# MainBoardV2.net
KiCad netlist of a schematic drawn in Altium Designer
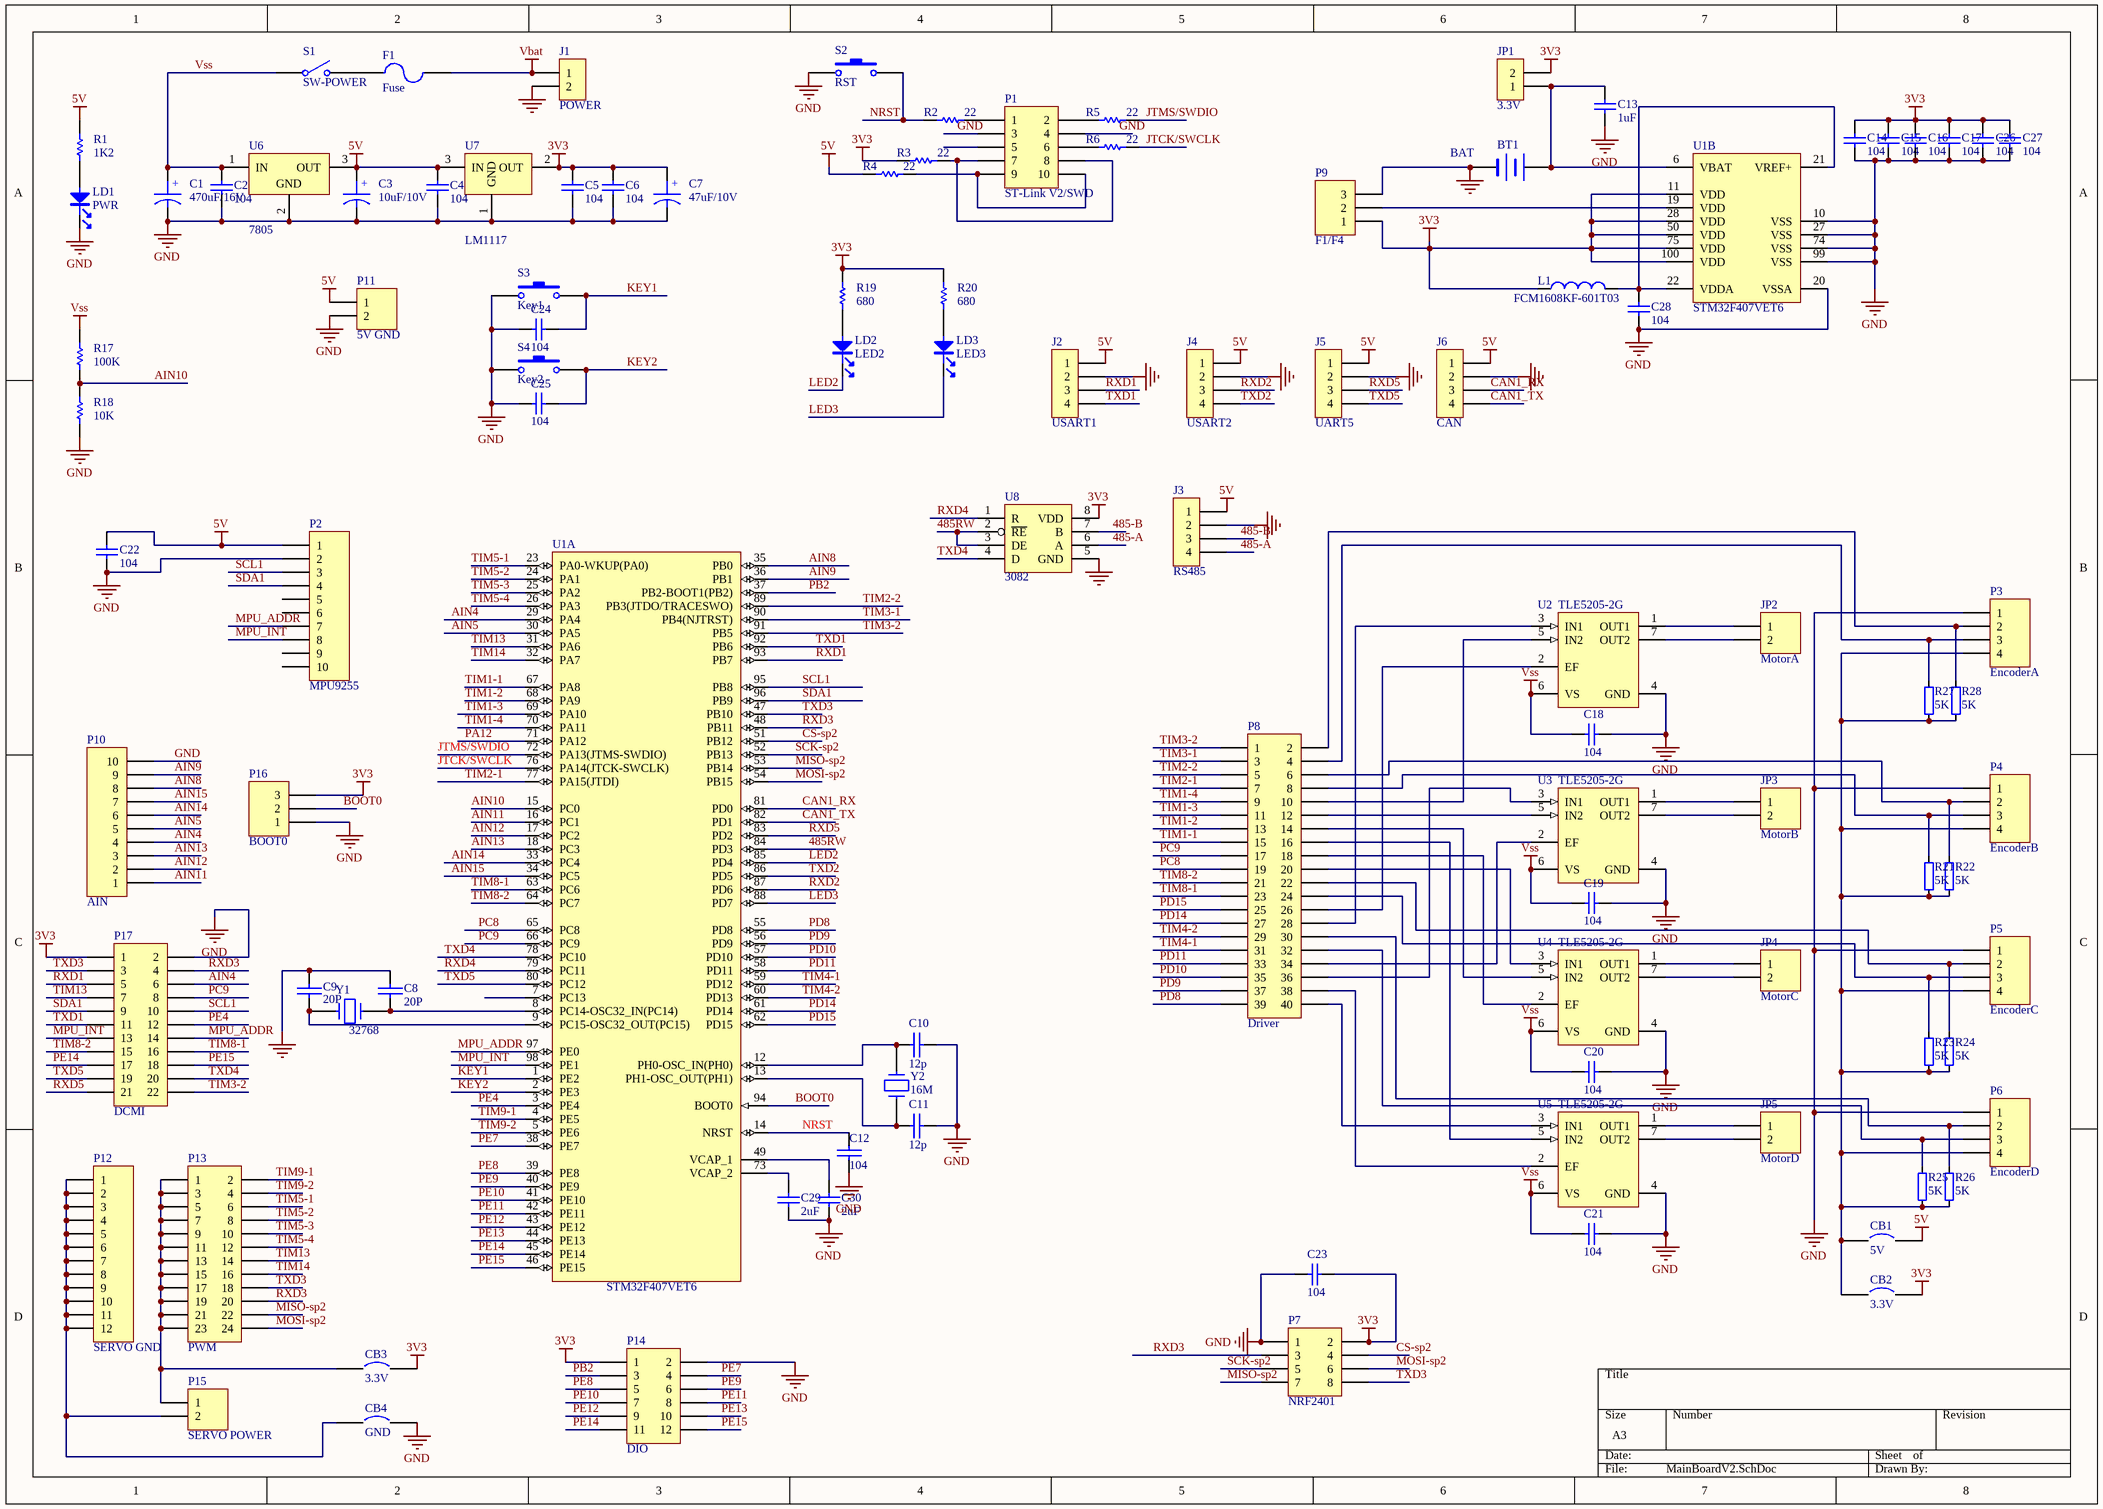
[diagram p0: MainBoardV2.SchDoc]

(export (version "E")
  (design (tool "Eeschema 10.0.6"))
  (components
    (comp (ref "BT1")
      (value "BAT")
      (footprint "SIP2 - duplicate")
      (description "Battery")
      (libsource (lib "*") (part "BATTERY"))
    )
    (comp (ref "C1") (value "470uF/16V") (footprint "RB2") (libsource (lib "SmartHome") (part "CAP POL")))
    (comp (ref "C2")
      (value "104")
      (description "Capacitor")
      (fields (field (name "Comment") "Cap") (field (name "PUBLISHER") "Altium Limited"))
      (libsource (lib "Miscellaneous Devices") (part "Cap"))
    )
    (comp (ref "C3") (value "10uF/10V") (footprint "RB2") (libsource (lib "SmartHome") (part "CAP POL")))
    (comp (ref "C4")
      (value "104")
      (description "Capacitor")
      (fields (field (name "Comment") "Cap") (field (name "PUBLISHER") "Altium Limited"))
      (libsource (lib "Miscellaneous Devices") (part "Cap"))
    )
    (comp (ref "C5")
      (value "104")
      (description "Capacitor")
      (fields (field (name "Comment") "Cap") (field (name "PUBLISHER") "Altium Limited"))
      (libsource (lib "Miscellaneous Devices") (part "Cap"))
    )
    (comp (ref "C6")
      (value "104")
      (description "Capacitor")
      (fields (field (name "Comment") "Cap") (field (name "PUBLISHER") "Altium Limited"))
      (libsource (lib "Miscellaneous Devices") (part "Cap"))
    )
    (comp (ref "C7") (value "47uF/10V") (footprint "RB2") (libsource (lib "SmartHome") (part "CAP POL")))
    (comp (ref "C8")
      (value "20P")
      (footprint "0603")
      (description "Capacitor")
      (libsource (lib "*") (part "CAP"))
    )
    (comp (ref "C9")
      (value "20P")
      (footprint "0603")
      (description "Capacitor")
      (libsource (lib "*") (part "CAP"))
    )
    (comp (ref "C10")
      (value "12p")
      (footprint "0603")
      (description "Capacitor")
      (libsource (lib "*") (part "CAP"))
    )
    (comp (ref "C11")
      (value "12p")
      (footprint "0603")
      (description "Capacitor")
      (libsource (lib "*") (part "CAP"))
    )
    (comp (ref "C12")
      (value "104")
      (footprint "0603")
      (description "Capacitor")
      (libsource (lib "*") (part "CAP"))
    )
    (comp (ref "C13")
      (value "1uF")
      (description "Capacitor")
      (fields (field (name "Comment") "Cap") (field (name "PUBLISHER") "Altium Limited"))
      (libsource (lib "Miscellaneous Devices") (part "Cap"))
    )
    (comp (ref "C14")
      (value "104")
      (description "Capacitor")
      (fields (field (name "Comment") "Cap") (field (name "PUBLISHER") "Altium Limited"))
      (libsource (lib "Miscellaneous Devices") (part "Cap"))
    )
    (comp (ref "C15")
      (value "104")
      (description "Capacitor")
      (fields (field (name "Comment") "Cap") (field (name "PUBLISHER") "Altium Limited"))
      (libsource (lib "Miscellaneous Devices") (part "Cap"))
    )
    (comp (ref "C16")
      (value "104")
      (description "Capacitor")
      (fields (field (name "Comment") "Cap") (field (name "PUBLISHER") "Altium Limited"))
      (libsource (lib "Miscellaneous Devices") (part "Cap"))
    )
    (comp (ref "C17")
      (value "104")
      (description "Capacitor")
      (fields (field (name "Comment") "Cap") (field (name "PUBLISHER") "Altium Limited"))
      (libsource (lib "Miscellaneous Devices") (part "Cap"))
    )
    (comp (ref "C18")
      (value "104")
      (description "Capacitor")
      (fields (field (name "Comment") "Cap") (field (name "PUBLISHER") "Altium Limited"))
      (libsource (lib "Miscellaneous Devices") (part "Cap"))
    )
    (comp (ref "C19")
      (value "104")
      (description "Capacitor")
      (fields (field (name "Comment") "Cap") (field (name "PUBLISHER") "Altium Limited"))
      (libsource (lib "Miscellaneous Devices") (part "Cap"))
    )
    (comp (ref "C20")
      (value "104")
      (description "Capacitor")
      (fields (field (name "Comment") "Cap") (field (name "PUBLISHER") "Altium Limited"))
      (libsource (lib "Miscellaneous Devices") (part "Cap"))
    )
    (comp (ref "C21")
      (value "104")
      (description "Capacitor")
      (fields (field (name "Comment") "Cap") (field (name "PUBLISHER") "Altium Limited"))
      (libsource (lib "Miscellaneous Devices") (part "Cap"))
    )
    (comp (ref "C22")
      (value "104")
      (description "Capacitor")
      (fields (field (name "Comment") "Cap") (field (name "PUBLISHER") "Altium Limited"))
      (libsource (lib "Miscellaneous Devices") (part "Cap"))
    )
    (comp (ref "C23")
      (value "104")
      (description "Capacitor")
      (fields (field (name "Comment") "Cap") (field (name "PUBLISHER") "Altium Limited"))
      (libsource (lib "Miscellaneous Devices") (part "Cap"))
    )
    (comp (ref "C24")
      (value "104")
      (description "Capacitor")
      (fields (field (name "Comment") "Cap") (field (name "PUBLISHER") "Altium Limited"))
      (libsource (lib "Miscellaneous Devices") (part "Cap"))
    )
    (comp (ref "C25")
      (value "104")
      (description "Capacitor")
      (fields (field (name "Comment") "Cap") (field (name "PUBLISHER") "Altium Limited"))
      (libsource (lib "Miscellaneous Devices") (part "Cap"))
    )
    (comp (ref "C26")
      (value "104")
      (description "Capacitor")
      (fields (field (name "Comment") "Cap") (field (name "PUBLISHER") "Altium Limited"))
      (libsource (lib "Miscellaneous Devices") (part "Cap"))
    )
    (comp (ref "C27")
      (value "104")
      (description "Capacitor")
      (fields (field (name "Comment") "Cap") (field (name "PUBLISHER") "Altium Limited"))
      (libsource (lib "Miscellaneous Devices") (part "Cap"))
    )
    (comp (ref "C28")
      (value "104")
      (description "Capacitor")
      (fields (field (name "Comment") "Cap") (field (name "PUBLISHER") "Altium Limited"))
      (libsource (lib "Miscellaneous Devices") (part "Cap"))
    )
    (comp (ref "C29")
      (value "2uF")
      (description "Capacitor")
      (fields (field (name "Comment") "Cap") (field (name "PUBLISHER") "Altium Limited"))
      (libsource (lib "Miscellaneous Devices") (part "Cap"))
    )
    (comp (ref "C30")
      (value "2uF")
      (description "Capacitor")
      (fields (field (name "Comment") "Cap") (field (name "PUBLISHER") "Altium Limited"))
      (libsource (lib "Miscellaneous Devices") (part "Cap"))
    )
    (comp (ref "CB1")
      (value "5V")
      (footprint "SIP2 - duplicate")
      (description "Circuit Breaker")
      (fields (field (name "PUBLISHER") "Altium Limited"))
      (libsource (lib "Miscellaneous Devices") (part "Circuit Breaker"))
    )
    (comp (ref "CB2")
      (value "3.3V")
      (footprint "SIP2 - duplicate")
      (description "Circuit Breaker")
      (fields (field (name "PUBLISHER") "Altium Limited"))
      (libsource (lib "Miscellaneous Devices") (part "Circuit Breaker"))
    )
    (comp (ref "CB3")
      (value "3.3V")
      (footprint "SIP2 - duplicate")
      (description "Circuit Breaker")
      (fields (field (name "PUBLISHER") "Altium Limited"))
      (libsource (lib "Miscellaneous Devices") (part "Circuit Breaker"))
    )
    (comp (ref "CB4")
      (value "GND")
      (footprint "SIP2 - duplicate")
      (description "Circuit Breaker")
      (fields (field (name "PUBLISHER") "Altium Limited"))
      (libsource (lib "Miscellaneous Devices") (part "Circuit Breaker"))
    )
    (comp (ref "F1")
      (value "Fuse")
      (footprint "1808Shell")
      (fields (field (name "PUBLISHER") "Altium Limited"))
      (libsource (lib "Miscellaneous Devices") (part "Fuse 2"))
    )
    (comp (ref "J1")
      (value "POWER")
      (footprint "SIP2-200")
      (description "Connector")
      (libsource (lib "") (part "CON2_1"))
    )
    (comp (ref "J2")
      (value "USART1")
      (footprint "sip4")
      (description "Connector")
      (libsource (lib "*") (part "CON4"))
    )
    (comp (ref "J3")
      (value "RS485")
      (footprint "sip4")
      (description "Connector")
      (libsource (lib "*") (part "CON4"))
    )
    (comp (ref "J4")
      (value "USART2")
      (footprint "sip4")
      (description "Connector")
      (libsource (lib "*") (part "CON4"))
    )
    (comp (ref "J5")
      (value "UART5")
      (footprint "sip4")
      (description "Connector")
      (libsource (lib "*") (part "CON4"))
    )
    (comp (ref "J6")
      (value "CAN")
      (footprint "sip4")
      (description "Connector")
      (libsource (lib "*") (part "CON4"))
    )
    (comp (ref "JP1")
      (value "3.3V")
      (footprint "SIP2 - duplicate")
      (description "Connector")
      (libsource (lib "*") (part "CON2"))
    )
    (comp (ref "JP2")
      (value "MotorA")
      (footprint "SIP2-150")
      (description "Header, 2-Pin")
      (fields (field (name "PUBLISHER") "Altium Limited"))
      (libsource (lib "Miscellaneous Connectors") (part "Header 2"))
    )
    (comp (ref "JP3")
      (value "MotorB")
      (footprint "SIP2-150")
      (description "Header, 2-Pin")
      (fields (field (name "PUBLISHER") "Altium Limited"))
      (libsource (lib "Miscellaneous Connectors") (part "Header 2"))
    )
    (comp (ref "JP4")
      (value "MotorC")
      (footprint "SIP2-150")
      (description "Header, 2-Pin")
      (fields (field (name "PUBLISHER") "Altium Limited"))
      (libsource (lib "Miscellaneous Connectors") (part "Header 2"))
    )
    (comp (ref "JP5")
      (value "MotorD")
      (footprint "SIP2-150")
      (description "Header, 2-Pin")
      (fields (field (name "PUBLISHER") "Altium Limited"))
      (libsource (lib "Miscellaneous Connectors") (part "Header 2"))
    )
    (comp (ref "L1")
      (value "FCM1608KF-601T03")
      (footprint "0603")
      (description "Inductor")
      (fields (field (name "PUBLISHER") "Altium Limited"))
      (libsource (lib "Miscellaneous Devices") (part "Inductor"))
    )
    (comp (ref "LD1") (value "PWR") (footprint "0603") (libsource (lib "MB963_1") (part "PHOTO")))
    (comp (ref "LD2") (value "LED2") (footprint "0603") (libsource (lib "MB963_1") (part "PHOTO")))
    (comp (ref "LD3") (value "LED3") (footprint "0603") (libsource (lib "MB963_1") (part "PHOTO")))
    (comp (ref "P1")
      (value "ST-Link V2/SWD")
      (footprint "HDR2X5")
      (description "Header, 5-Pin, Dual row")
      (fields (field (name "PUBLISHER") "Altium Limited"))
      (libsource (lib "Miscellaneous Connectors") (part "Header 5X2"))
    )
    (comp (ref "P2")
      (value "MPU9255")
      (footprint "HDR1X10")
      (description "Header, 10-Pin")
      (fields (field (name "PUBLISHER") "Altium Limited"))
      (libsource (lib "") (part "Header 10_1"))
    )
    (comp (ref "P3")
      (value "EncoderA")
      (footprint "SIP4-150")
      (description "Header, 4-Pin")
      (fields (field (name "PUBLISHER") "Altium Limited"))
      (libsource (lib "Miscellaneous Connectors") (part "Header 4"))
    )
    (comp (ref "P4")
      (value "EncoderB")
      (footprint "SIP4-150")
      (description "Header, 4-Pin")
      (fields (field (name "PUBLISHER") "Altium Limited"))
      (libsource (lib "Miscellaneous Connectors") (part "Header 4"))
    )
    (comp (ref "P5")
      (value "EncoderC")
      (footprint "SIP4-150")
      (description "Header, 4-Pin")
      (fields (field (name "PUBLISHER") "Altium Limited"))
      (libsource (lib "Miscellaneous Connectors") (part "Header 4"))
    )
    (comp (ref "P6")
      (value "EncoderD")
      (footprint "SIP4-150")
      (description "Header, 4-Pin")
      (fields (field (name "PUBLISHER") "Altium Limited"))
      (libsource (lib "Miscellaneous Connectors") (part "Header 4"))
    )
    (comp (ref "P7")
      (value "NRF2401")
      (footprint "HDR2X4")
      (description "Header, 4-Pin, Dual row")
      (fields (field (name "PUBLISHER") "Altium Limited"))
      (libsource (lib "Miscellaneous Connectors") (part "Header 4X2"))
    )
    (comp (ref "P8")
      (value "Driver")
      (footprint "HDR2X20")
      (description "Header, 20-Pin, Dual row")
      (fields (field (name "PUBLISHER") "Altium Limited"))
      (libsource (lib "Miscellaneous Connectors") (part "Header 20X2"))
    )
    (comp (ref "P9")
      (value "F1/F4")
      (footprint "HDR1X3")
      (description "Header, 3-Pin")
      (fields (field (name "PUBLISHER") "Altium Limited"))
      (libsource (lib "Miscellaneous Connectors") (part "Header 3"))
    )
    (comp (ref "P10")
      (value "AIN")
      (footprint "HDR1X10")
      (description "Header, 10-Pin")
      (fields (field (name "PUBLISHER") "Altium Limited"))
      (libsource (lib "Miscellaneous Connectors") (part "Header 10"))
    )
    (comp (ref "P11")
      (value "5V GND")
      (footprint "SIP2-150")
      (description "Header, 2-Pin")
      (fields (field (name "PUBLISHER") "Altium Limited"))
      (libsource (lib "Miscellaneous Connectors") (part "Header 2"))
    )
    (comp (ref "P12")
      (value "SERVO GND")
      (footprint "HDR1X12")
      (description "Header, 12-Pin")
      (fields (field (name "PUBLISHER") "Altium Limited"))
      (libsource (lib "Miscellaneous Connectors") (part "Header 12"))
    )
    (comp (ref "P13")
      (value "PWM")
      (footprint "HDR2X12")
      (description "Header, 12-Pin, Dual row")
      (fields (field (name "PUBLISHER") "Altium Limited"))
      (libsource (lib "Miscellaneous Connectors") (part "Header 12X2"))
    )
    (comp (ref "P14")
      (value "DIO")
      (footprint "HDR2X6")
      (description "Header, 6-Pin, Dual row")
      (fields (field (name "PUBLISHER") "Altium Limited"))
      (libsource (lib "Miscellaneous Connectors") (part "Header 6X2"))
    )
    (comp (ref "P15")
      (value "SERVO POWER")
      (footprint "2p150")
      (description "Header, 2-Pin")
      (fields (field (name "PUBLISHER") "Altium Limited"))
      (libsource (lib "Miscellaneous Connectors") (part "Header 2"))
    )
    (comp (ref "P16")
      (value "BOOT0")
      (footprint "HDR1X3")
      (description "Header, 3-Pin")
      (fields (field (name "PUBLISHER") "Altium Limited"))
      (libsource (lib "Miscellaneous Connectors") (part "Header 3"))
    )
    (comp (ref "P17")
      (value "DCMI")
      (footprint "HDR2X11")
      (description "Header, 11-Pin, Dual row")
      (fields (field (name "PUBLISHER") "Altium Limited"))
      (libsource (lib "Miscellaneous Connectors") (part "Header 11X2"))
    )
    (comp (ref "R1")
      (value "1K2")
      (footprint "0603")
      (description "Resistor 0402 / 0603 / 0805")
      (libsource (lib "MCD_TOOLS") (part "Resistor_ST"))
    )
    (comp (ref "R2")
      (value "22")
      (footprint "0603")
      (description "Resistor 0402 / 0603 / 0805")
      (libsource (lib "Miscellaneous Devices") (part "Res1"))
    )
    (comp (ref "R3")
      (value "22")
      (footprint "0603")
      (description "Resistor 0402 / 0603 / 0805")
      (libsource (lib "Miscellaneous Devices") (part "Res1"))
    )
    (comp (ref "R4")
      (value "22")
      (footprint "0603")
      (description "Resistor 0402 / 0603 / 0805")
      (libsource (lib "Miscellaneous Devices") (part "Res1"))
    )
    (comp (ref "R5")
      (value "22")
      (footprint "0603")
      (description "Resistor 0402 / 0603 / 0805")
      (libsource (lib "Miscellaneous Devices") (part "Res1"))
    )
    (comp (ref "R6")
      (value "22")
      (footprint "0603")
      (description "Resistor 0402 / 0603 / 0805")
      (libsource (lib "Miscellaneous Devices") (part "Res1"))
    )
    (comp (ref "R17")
      (value "100K")
      (footprint "0603")
      (description "Resistor 0402 / 0603 / 0805")
      (libsource (lib "MCD_TOOLS") (part "Resistor_ST"))
    )
    (comp (ref "R18")
      (value "10K")
      (footprint "0603")
      (description "Resistor 0402 / 0603 / 0805")
      (libsource (lib "MCD_TOOLS") (part "Resistor_ST"))
    )
    (comp (ref "R19")
      (value "680")
      (footprint "0603")
      (description "Resistor 0402 / 0603 / 0805")
      (libsource (lib "MCD_TOOLS") (part "Resistor_ST"))
    )
    (comp (ref "R20")
      (value "680")
      (footprint "0603")
      (description "Resistor 0402 / 0603 / 0805")
      (libsource (lib "MCD_TOOLS") (part "Resistor_ST"))
    )
    (comp (ref "R21") (value "5K") (footprint "0603") (libsource (lib "电阻") (part "RES")))
    (comp (ref "R22") (value "5K") (footprint "0603") (libsource (lib "电阻") (part "RES")))
    (comp (ref "R23") (value "5K") (footprint "0603") (libsource (lib "电阻") (part "RES")))
    (comp (ref "R24") (value "5K") (footprint "0603") (libsource (lib "电阻") (part "RES")))
    (comp (ref "R25") (value "5K") (footprint "0603") (libsource (lib "电阻") (part "RES")))
    (comp (ref "R26") (value "5K") (footprint "0603") (libsource (lib "电阻") (part "RES")))
    (comp (ref "R27") (value "5K") (footprint "0603") (libsource (lib "电阻") (part "RES")))
    (comp (ref "R28") (value "5K") (footprint "0603") (libsource (lib "电阻") (part "RES")))
    (comp (ref "S1")
      (value "SW-POWER")
      (footprint "SPST-2")
      (description "Single-Pole, Single-Throw Switch")
      (fields (field (name "PUBLISHER") "Altium Limited"))
      (libsource (lib "Miscellaneous Devices") (part "SW-SPST"))
    )
    (comp (ref "S2")
      (value "RST")
      (footprint "key2")
      (description "Switch")
      (fields (field (name "PUBLISHER") "Altium Limited"))
      (libsource (lib "Miscellaneous Devices") (part "SW-PB"))
    )
    (comp (ref "S3")
      (value "Key1")
      (footprint "key2")
      (description "Switch")
      (fields (field (name "PUBLISHER") "Altium Limited"))
      (libsource (lib "Miscellaneous Devices") (part "SW-PB"))
    )
    (comp (ref "S4")
      (value "Key2")
      (footprint "key2")
      (description "Switch")
      (fields (field (name "PUBLISHER") "Altium Limited"))
      (libsource (lib "Miscellaneous Devices") (part "SW-PB"))
    )
    (comp (ref "U1")
      (value "STM32F407VET6")
      (footprint "QUAD100")
      (fields (field (name "MANUFACTURER") "STMicroelectronics"))
      (libsource (lib "STMicroelectronics STM32 F4") (part "STM32F407VET6"))
    )
    (comp (ref "U2")
      (value "TLE5205-2G")
      (footprint "INF-PG-TO263-7-1_L")
      (description "5 A H-Bridge for DC-Motor Applications, 6 to 40 V, 220 mOhm RDS(on), PG-TO263-7-1, Reel, Green")
      (fields (field (name "MANUFACTURER") "Infineon"))
      (libsource (lib "TLE5205-2G") (part "TLE5205-2G"))
    )
    (comp (ref "U3")
      (value "TLE5205-2G")
      (footprint "INF-PG-TO263-7-1_L")
      (description "5 A H-Bridge for DC-Motor Applications, 6 to 40 V, 220 mOhm RDS(on), PG-TO263-7-1, Reel, Green")
      (fields (field (name "MANUFACTURER") "Infineon"))
      (libsource (lib "TLE5205-2G") (part "TLE5205-2G"))
    )
    (comp (ref "U4")
      (value "TLE5205-2G")
      (footprint "INF-PG-TO263-7-1_L")
      (description "5 A H-Bridge for DC-Motor Applications, 6 to 40 V, 220 mOhm RDS(on), PG-TO263-7-1, Reel, Green")
      (fields (field (name "MANUFACTURER") "Infineon"))
      (libsource (lib "TLE5205-2G") (part "TLE5205-2G"))
    )
    (comp (ref "U5")
      (value "TLE5205-2G")
      (footprint "INF-PG-TO263-7-1_L")
      (description "5 A H-Bridge for DC-Motor Applications, 6 to 40 V, 220 mOhm RDS(on), PG-TO263-7-1, Reel, Green")
      (fields (field (name "MANUFACTURER") "Infineon"))
      (libsource (lib "TLE5205-2G") (part "TLE5205-2G"))
    )
    (comp (ref "U6")
      (value "7805")
      (footprint "ktt")
      (description "3-Terminal Positive Regulator")
      (fields (field (name "PUBLISHER") "Altium Limited"))
      (libsource (lib "TI Power Mgt Voltage Regulator") (part "LM330KC"))
    )
    (comp (ref "U7") (value "LM1117") (footprint "SPP3") (libsource (lib "*") (part "LM1117")))
    (comp (ref "U8") (value "3082") (footprint "so-8") (libsource (lib "*") (part "75176")))
    (comp (ref "Y1")
      (value "32768")
      (footprint "sip2")
      (description "Crystal")
      (libsource (lib "*") (part "CRYSTAL"))
    )
    (comp (ref "Y2")
      (value "16M")
      (footprint "XTAL1")
      (description "Crystal")
      (libsource (lib "*") (part "CRYSTAL"))
    )
  )
  (nets
    (net (code "1") (name "/485-A") (class "Default")
      (node (ref "J3") (pin "4") (pinfunction "4_4") (pintype "passive"))
      (node (ref "U8") (pin "6") (pinfunction "A_6") (pintype "passive"))
    )
    (net (code "2") (name "/485-B") (class "Default")
      (node (ref "J3") (pin "3") (pinfunction "3_3") (pintype "passive"))
      (node (ref "U8") (pin "7") (pinfunction "B_7") (pintype "passive"))
    )
    (net (code "3") (name "/485RW") (class "Default")
      (node (ref "U1") (pin "84") (pinfunction "PD3_84") (pintype "bidirectional"))
      (node (ref "U8") (pin "2") (pinfunction "~{RE}_2") (pintype "passive"))
      (node (ref "U8") (pin "3") (pinfunction "DE_3") (pintype "passive"))
    )
    (net (code "4") (name "/AIN4") (class "Default")
      (node (ref "P10") (pin "4") (pinfunction "4_4") (pintype "passive"))
      (node (ref "P17") (pin "6") (pinfunction "6_6") (pintype "passive"))
      (node (ref "U1") (pin "29") (pinfunction "PA4_29") (pintype "bidirectional"))
    )
    (net (code "5") (name "/AIN5") (class "Default")
      (node (ref "P10") (pin "5") (pinfunction "5_5") (pintype "passive"))
      (node (ref "U1") (pin "30") (pinfunction "PA5_30") (pintype "bidirectional"))
    )
    (net (code "6") (name "/AIN8") (class "Default")
      (node (ref "P10") (pin "8") (pinfunction "8_8") (pintype "passive"))
      (node (ref "U1") (pin "35") (pinfunction "PB0_35") (pintype "bidirectional"))
    )
    (net (code "7") (name "/AIN9") (class "Default")
      (node (ref "P10") (pin "9") (pinfunction "9_9") (pintype "passive"))
      (node (ref "U1") (pin "36") (pinfunction "PB1_36") (pintype "bidirectional"))
    )
    (net (code "8") (name "/AIN10") (class "Default")
      (node (ref "R17") (pin "1") (pinfunction "1_1") (pintype "passive"))
      (node (ref "R18") (pin "2") (pinfunction "2_2") (pintype "passive"))
      (node (ref "U1") (pin "15") (pinfunction "PC0_15") (pintype "bidirectional"))
    )
    (net (code "9") (name "/AIN11") (class "Default")
      (node (ref "P10") (pin "1") (pinfunction "1_1") (pintype "passive"))
      (node (ref "U1") (pin "16") (pinfunction "PC1_16") (pintype "bidirectional"))
    )
    (net (code "10") (name "/AIN12") (class "Default")
      (node (ref "P10") (pin "2") (pinfunction "2_2") (pintype "passive"))
      (node (ref "U1") (pin "17") (pinfunction "PC2_17") (pintype "bidirectional"))
    )
    (net (code "11") (name "/AIN13") (class "Default")
      (node (ref "P10") (pin "3") (pinfunction "3_3") (pintype "passive"))
      (node (ref "U1") (pin "18") (pinfunction "PC3_18") (pintype "bidirectional"))
    )
    (net (code "12") (name "/AIN14") (class "Default")
      (node (ref "P10") (pin "6") (pinfunction "6_6") (pintype "passive"))
      (node (ref "U1") (pin "33") (pinfunction "PC4_33") (pintype "bidirectional"))
    )
    (net (code "13") (name "/AIN15") (class "Default")
      (node (ref "P10") (pin "7") (pinfunction "7_7") (pintype "passive"))
      (node (ref "U1") (pin "34") (pinfunction "PC5_34") (pintype "bidirectional"))
    )
    (net (code "14") (name "/BOOT0") (class "Default")
      (node (ref "P16") (pin "2") (pinfunction "2_2") (pintype "passive"))
      (node (ref "U1") (pin "94") (pinfunction "BOOT0_94") (pintype "input"))
    )
    (net (code "15") (name "/CAN1_RX") (class "Default")
      (node (ref "J6") (pin "3") (pinfunction "3_3") (pintype "passive"))
      (node (ref "U1") (pin "81") (pinfunction "PD0_81") (pintype "bidirectional"))
    )
    (net (code "16") (name "/CAN1_TX") (class "Default")
      (node (ref "J6") (pin "4") (pinfunction "4_4") (pintype "passive"))
      (node (ref "U1") (pin "82") (pinfunction "PD1_82") (pintype "bidirectional"))
    )
    (net (code "17") (name "/CS-sp2") (class "Default")
      (node (ref "P7") (pin "4") (pinfunction "4_4") (pintype "passive"))
      (node (ref "U1") (pin "51") (pinfunction "PB12_51") (pintype "bidirectional"))
    )
    (net (code "18") (name "/JTCK{slash}SWCLK") (class "Default")
      (node (ref "R6") (pin "2") (pinfunction "2_2") (pintype "passive"))
      (node (ref "U1") (pin "76") (pinfunction "PA14(JTCK-SWCLK)_76") (pintype "bidirectional"))
    )
    (net (code "19") (name "/JTMS{slash}SWDIO") (class "Default")
      (node (ref "R5") (pin "2") (pinfunction "2_2") (pintype "passive"))
      (node (ref "U1") (pin "72") (pinfunction "PA13(JTMS-SWDIO)_72") (pintype "bidirectional"))
    )
    (net (code "20") (name "/KEY1") (class "Default")
      (node (ref "C24") (pin "2") (pinfunction "2_2") (pintype "passive"))
      (node (ref "S3") (pin "2") (pinfunction "2_2") (pintype "passive"))
      (node (ref "U1") (pin "1") (pinfunction "PE2_1") (pintype "bidirectional"))
    )
    (net (code "21") (name "/KEY2") (class "Default")
      (node (ref "C25") (pin "2") (pinfunction "2_2") (pintype "passive"))
      (node (ref "S4") (pin "2") (pinfunction "2_2") (pintype "passive"))
      (node (ref "U1") (pin "2") (pinfunction "PE3_2") (pintype "bidirectional"))
    )
    (net (code "22") (name "/LED2") (class "Default")
      (node (ref "LD2") (pin "2") (pintype "passive"))
      (node (ref "U1") (pin "85") (pinfunction "PD4_85") (pintype "bidirectional"))
    )
    (net (code "23") (name "/LED3") (class "Default")
      (node (ref "LD3") (pin "2") (pintype "passive"))
      (node (ref "U1") (pin "88") (pinfunction "PD7_88") (pintype "bidirectional"))
    )
    (net (code "24") (name "/MISO-sp2") (class "Default")
      (node (ref "P13") (pin "22") (pinfunction "22_22") (pintype "passive"))
      (node (ref "P7") (pin "7") (pinfunction "7_7") (pintype "passive"))
      (node (ref "U1") (pin "53") (pinfunction "PB14_53") (pintype "bidirectional"))
    )
    (net (code "25") (name "/MOSI-sp2") (class "Default")
      (node (ref "P13") (pin "24") (pinfunction "24_24") (pintype "passive"))
      (node (ref "P7") (pin "6") (pinfunction "6_6") (pintype "passive"))
      (node (ref "U1") (pin "54") (pinfunction "PB15_54") (pintype "bidirectional"))
    )
    (net (code "26") (name "/MPU_ADDR") (class "Default")
      (node (ref "P17") (pin "14") (pinfunction "14_14") (pintype "passive"))
      (node (ref "P2") (pin "7") (pinfunction "7_7") (pintype "passive"))
      (node (ref "U1") (pin "97") (pinfunction "PE0_97") (pintype "bidirectional"))
    )
    (net (code "27") (name "/MPU_INT") (class "Default")
      (node (ref "P17") (pin "13") (pinfunction "13_13") (pintype "passive"))
      (node (ref "P2") (pin "8") (pinfunction "8_8") (pintype "passive"))
      (node (ref "U1") (pin "98") (pinfunction "PE1_98") (pintype "bidirectional"))
    )
    (net (code "28") (name "/NRST") (class "Default")
      (node (ref "C12") (pin "1") (pinfunction "1_1") (pintype "passive"))
      (node (ref "R2") (pin "1") (pinfunction "1_1") (pintype "passive"))
      (node (ref "S2") (pin "2") (pinfunction "2_2") (pintype "passive"))
      (node (ref "U1") (pin "14") (pinfunction "NRST_14") (pintype "bidirectional"))
    )
    (net (code "29") (name "/PA12") (class "Default")
      (node (ref "U1") (pin "71") (pinfunction "PA12_71") (pintype "bidirectional"))
    )
    (net (code "30") (name "/PB2") (class "Default")
      (node (ref "P14") (pin "3") (pinfunction "3_3") (pintype "passive"))
      (node (ref "U1") (pin "37") (pinfunction "PB2-BOOT1(PB2)_37") (pintype "bidirectional"))
    )
    (net (code "31") (name "/PC8") (class "Default")
      (node (ref "P8") (pin "19") (pinfunction "19_19") (pintype "passive"))
      (node (ref "U1") (pin "65") (pinfunction "PC8_65") (pintype "bidirectional"))
    )
    (net (code "32") (name "/PC9") (class "Default")
      (node (ref "P17") (pin "8") (pinfunction "8_8") (pintype "passive"))
      (node (ref "P8") (pin "17") (pinfunction "17_17") (pintype "passive"))
      (node (ref "U1") (pin "66") (pinfunction "PC9_66") (pintype "bidirectional"))
    )
    (net (code "33") (name "/PD8") (class "Default")
      (node (ref "P8") (pin "39") (pinfunction "39_39") (pintype "passive"))
      (node (ref "U1") (pin "55") (pinfunction "PD8_55") (pintype "bidirectional"))
    )
    (net (code "34") (name "/PD9") (class "Default")
      (node (ref "P8") (pin "37") (pinfunction "37_37") (pintype "passive"))
      (node (ref "U1") (pin "56") (pinfunction "PD9_56") (pintype "bidirectional"))
    )
    (net (code "35") (name "/PD10") (class "Default")
      (node (ref "P8") (pin "35") (pinfunction "35_35") (pintype "passive"))
      (node (ref "U1") (pin "57") (pinfunction "PD10_57") (pintype "bidirectional"))
    )
    (net (code "36") (name "/PD11") (class "Default")
      (node (ref "P8") (pin "33") (pinfunction "33_33") (pintype "passive"))
      (node (ref "U1") (pin "58") (pinfunction "PD11_58") (pintype "bidirectional"))
    )
    (net (code "37") (name "/PD14") (class "Default")
      (node (ref "P8") (pin "27") (pinfunction "27_27") (pintype "passive"))
      (node (ref "U1") (pin "61") (pinfunction "PD14_61") (pintype "bidirectional"))
    )
    (net (code "38") (name "/PD15") (class "Default")
      (node (ref "P8") (pin "25") (pinfunction "25_25") (pintype "passive"))
      (node (ref "U1") (pin "62") (pinfunction "PD15_62") (pintype "bidirectional"))
    )
    (net (code "39") (name "/PE4") (class "Default")
      (node (ref "P17") (pin "12") (pinfunction "12_12") (pintype "passive"))
      (node (ref "U1") (pin "3") (pinfunction "PE4_3") (pintype "bidirectional"))
    )
    (net (code "40") (name "/PE7") (class "Default")
      (node (ref "P14") (pin "4") (pinfunction "4_4") (pintype "passive"))
      (node (ref "U1") (pin "38") (pinfunction "PE7_38") (pintype "bidirectional"))
    )
    (net (code "41") (name "/PE8") (class "Default")
      (node (ref "P14") (pin "5") (pinfunction "5_5") (pintype "passive"))
      (node (ref "U1") (pin "39") (pinfunction "PE8_39") (pintype "bidirectional"))
    )
    (net (code "42") (name "/PE9") (class "Default")
      (node (ref "P14") (pin "6") (pinfunction "6_6") (pintype "passive"))
      (node (ref "U1") (pin "40") (pinfunction "PE9_40") (pintype "bidirectional"))
    )
    (net (code "43") (name "/PE10") (class "Default")
      (node (ref "P14") (pin "7") (pinfunction "7_7") (pintype "passive"))
      (node (ref "U1") (pin "41") (pinfunction "PE10_41") (pintype "bidirectional"))
    )
    (net (code "44") (name "/PE11") (class "Default")
      (node (ref "P14") (pin "8") (pinfunction "8_8") (pintype "passive"))
      (node (ref "U1") (pin "42") (pinfunction "PE11_42") (pintype "bidirectional"))
    )
    (net (code "45") (name "/PE12") (class "Default")
      (node (ref "P14") (pin "9") (pinfunction "9_9") (pintype "passive"))
      (node (ref "U1") (pin "43") (pinfunction "PE12_43") (pintype "bidirectional"))
    )
    (net (code "46") (name "/PE13") (class "Default")
      (node (ref "P14") (pin "10") (pinfunction "10_10") (pintype "passive"))
      (node (ref "U1") (pin "44") (pinfunction "PE13_44") (pintype "bidirectional"))
    )
    (net (code "47") (name "/PE14") (class "Default")
      (node (ref "P14") (pin "11") (pinfunction "11_11") (pintype "passive"))
      (node (ref "P17") (pin "17") (pinfunction "17_17") (pintype "passive"))
      (node (ref "U1") (pin "45") (pinfunction "PE14_45") (pintype "bidirectional"))
    )
    (net (code "48") (name "/PE15") (class "Default")
      (node (ref "P14") (pin "12") (pinfunction "12_12") (pintype "passive"))
      (node (ref "P17") (pin "18") (pinfunction "18_18") (pintype "passive"))
      (node (ref "U1") (pin "46") (pinfunction "PE15_46") (pintype "bidirectional"))
    )
    (net (code "49") (name "/RXD1") (class "Default")
      (node (ref "J2") (pin "3") (pinfunction "3_3") (pintype "passive"))
      (node (ref "P17") (pin "5") (pinfunction "5_5") (pintype "passive"))
      (node (ref "U1") (pin "93") (pinfunction "PB7_93") (pintype "bidirectional"))
    )
    (net (code "50") (name "/RXD2") (class "Default")
      (node (ref "J4") (pin "3") (pinfunction "3_3") (pintype "passive"))
      (node (ref "U1") (pin "87") (pinfunction "PD6_87") (pintype "bidirectional"))
    )
    (net (code "51") (name "/RXD3") (class "Default")
      (node (ref "P13") (pin "20") (pinfunction "20_20") (pintype "passive"))
      (node (ref "P17") (pin "4") (pinfunction "4_4") (pintype "passive"))
      (node (ref "P7") (pin "3") (pinfunction "3_3") (pintype "passive"))
      (node (ref "U1") (pin "48") (pinfunction "PB11_48") (pintype "bidirectional"))
    )
    (net (code "52") (name "/RXD4") (class "Default")
      (node (ref "U1") (pin "79") (pinfunction "PC11_79") (pintype "bidirectional"))
      (node (ref "U8") (pin "1") (pinfunction "R_1") (pintype "passive"))
    )
    (net (code "53") (name "/RXD5") (class "Default")
      (node (ref "J5") (pin "3") (pinfunction "3_3") (pintype "passive"))
      (node (ref "P17") (pin "21") (pinfunction "21_21") (pintype "passive"))
      (node (ref "U1") (pin "83") (pinfunction "PD2_83") (pintype "bidirectional"))
    )
    (net (code "54") (name "/SCK-sp2") (class "Default")
      (node (ref "P7") (pin "5") (pinfunction "5_5") (pintype "passive"))
      (node (ref "U1") (pin "52") (pinfunction "PB13_52") (pintype "bidirectional"))
    )
    (net (code "55") (name "/SCL1") (class "Default")
      (node (ref "P17") (pin "10") (pinfunction "10_10") (pintype "passive"))
      (node (ref "P2") (pin "3") (pinfunction "3_3") (pintype "passive"))
      (node (ref "U1") (pin "95") (pinfunction "PB8_95") (pintype "bidirectional"))
    )
    (net (code "56") (name "/SDA1") (class "Default")
      (node (ref "P17") (pin "9") (pinfunction "9_9") (pintype "passive"))
      (node (ref "P2") (pin "4") (pinfunction "4_4") (pintype "passive"))
      (node (ref "U1") (pin "96") (pinfunction "PB9_96") (pintype "bidirectional"))
    )
    (net (code "57") (name "/TIM1-1") (class "Default")
      (node (ref "P8") (pin "15") (pinfunction "15_15") (pintype "passive"))
      (node (ref "U1") (pin "67") (pinfunction "PA8_67") (pintype "bidirectional"))
    )
    (net (code "58") (name "/TIM1-2") (class "Default")
      (node (ref "P8") (pin "13") (pinfunction "13_13") (pintype "passive"))
      (node (ref "U1") (pin "68") (pinfunction "PA9_68") (pintype "bidirectional"))
    )
    (net (code "59") (name "/TIM1-3") (class "Default")
      (node (ref "P8") (pin "11") (pinfunction "11_11") (pintype "passive"))
      (node (ref "U1") (pin "69") (pinfunction "PA10_69") (pintype "bidirectional"))
    )
    (net (code "60") (name "/TIM1-4") (class "Default")
      (node (ref "P8") (pin "9") (pinfunction "9_9") (pintype "passive"))
      (node (ref "U1") (pin "70") (pinfunction "PA11_70") (pintype "bidirectional"))
    )
    (net (code "61") (name "/TIM2-1") (class "Default")
      (node (ref "P8") (pin "7") (pinfunction "7_7") (pintype "passive"))
      (node (ref "U1") (pin "77") (pinfunction "PA15(JTDI)_77") (pintype "bidirectional"))
    )
    (net (code "62") (name "/TIM2-2") (class "Default")
      (node (ref "P8") (pin "5") (pinfunction "5_5") (pintype "passive"))
      (node (ref "U1") (pin "89") (pinfunction "PB3(JTDO/TRACESWO)_89") (pintype "bidirectional"))
    )
    (net (code "63") (name "/TIM3-1") (class "Default")
      (node (ref "P8") (pin "3") (pinfunction "3_3") (pintype "passive"))
      (node (ref "U1") (pin "90") (pinfunction "PB4(NJTRST)_90") (pintype "bidirectional"))
    )
    (net (code "64") (name "/TIM3-2") (class "Default")
      (node (ref "P17") (pin "22") (pinfunction "22_22") (pintype "passive"))
      (node (ref "P8") (pin "1") (pinfunction "1_1") (pintype "passive"))
      (node (ref "U1") (pin "91") (pinfunction "PB5_91") (pintype "bidirectional"))
    )
    (net (code "65") (name "/TIM4-1") (class "Default")
      (node (ref "P8") (pin "31") (pinfunction "31_31") (pintype "passive"))
      (node (ref "U1") (pin "59") (pinfunction "PD12_59") (pintype "bidirectional"))
    )
    (net (code "66") (name "/TIM4-2") (class "Default")
      (node (ref "P8") (pin "29") (pinfunction "29_29") (pintype "passive"))
      (node (ref "U1") (pin "60") (pinfunction "PD13_60") (pintype "bidirectional"))
    )
    (net (code "67") (name "/TIM5-1") (class "Default")
      (node (ref "P13") (pin "6") (pinfunction "6_6") (pintype "passive"))
      (node (ref "U1") (pin "23") (pinfunction "PA0-WKUP(PA0)_23") (pintype "bidirectional"))
    )
    (net (code "68") (name "/TIM5-2") (class "Default")
      (node (ref "P13") (pin "8") (pinfunction "8_8") (pintype "passive"))
      (node (ref "U1") (pin "24") (pinfunction "PA1_24") (pintype "bidirectional"))
    )
    (net (code "69") (name "/TIM5-3") (class "Default")
      (node (ref "P13") (pin "10") (pinfunction "10_10") (pintype "passive"))
      (node (ref "U1") (pin "25") (pinfunction "PA2_25") (pintype "bidirectional"))
    )
    (net (code "70") (name "/TIM5-4") (class "Default")
      (node (ref "P13") (pin "12") (pinfunction "12_12") (pintype "passive"))
      (node (ref "U1") (pin "26") (pinfunction "PA3_26") (pintype "bidirectional"))
    )
    (net (code "71") (name "/TIM8-1") (class "Default")
      (node (ref "P17") (pin "16") (pinfunction "16_16") (pintype "passive"))
      (node (ref "P8") (pin "23") (pinfunction "23_23") (pintype "passive"))
      (node (ref "U1") (pin "63") (pinfunction "PC6_63") (pintype "bidirectional"))
    )
    (net (code "72") (name "/TIM8-2") (class "Default")
      (node (ref "P17") (pin "15") (pinfunction "15_15") (pintype "passive"))
      (node (ref "P8") (pin "21") (pinfunction "21_21") (pintype "passive"))
      (node (ref "U1") (pin "64") (pinfunction "PC7_64") (pintype "bidirectional"))
    )
    (net (code "73") (name "/TIM9-1") (class "Default")
      (node (ref "P13") (pin "2") (pinfunction "2_2") (pintype "passive"))
      (node (ref "U1") (pin "4") (pinfunction "PE5_4") (pintype "bidirectional"))
    )
    (net (code "74") (name "/TIM9-2") (class "Default")
      (node (ref "P13") (pin "4") (pinfunction "4_4") (pintype "passive"))
      (node (ref "U1") (pin "5") (pinfunction "PE6_5") (pintype "bidirectional"))
    )
    (net (code "75") (name "/TIM13") (class "Default")
      (node (ref "P13") (pin "14") (pinfunction "14_14") (pintype "passive"))
      (node (ref "P17") (pin "7") (pinfunction "7_7") (pintype "passive"))
      (node (ref "U1") (pin "31") (pinfunction "PA6_31") (pintype "bidirectional"))
    )
    (net (code "76") (name "/TIM14") (class "Default")
      (node (ref "P13") (pin "16") (pinfunction "16_16") (pintype "passive"))
      (node (ref "U1") (pin "32") (pinfunction "PA7_32") (pintype "bidirectional"))
    )
    (net (code "77") (name "/TXD1") (class "Default")
      (node (ref "J2") (pin "4") (pinfunction "4_4") (pintype "passive"))
      (node (ref "P17") (pin "11") (pinfunction "11_11") (pintype "passive"))
      (node (ref "U1") (pin "92") (pinfunction "PB6_92") (pintype "bidirectional"))
    )
    (net (code "78") (name "/TXD2") (class "Default")
      (node (ref "J4") (pin "4") (pinfunction "4_4") (pintype "passive"))
      (node (ref "U1") (pin "86") (pinfunction "PD5_86") (pintype "bidirectional"))
    )
    (net (code "79") (name "/TXD3") (class "Default")
      (node (ref "P13") (pin "18") (pinfunction "18_18") (pintype "passive"))
      (node (ref "P17") (pin "3") (pinfunction "3_3") (pintype "passive"))
      (node (ref "P7") (pin "8") (pinfunction "8_8") (pintype "passive"))
      (node (ref "U1") (pin "47") (pinfunction "PB10_47") (pintype "bidirectional"))
    )
    (net (code "80") (name "/TXD4") (class "Default")
      (node (ref "P17") (pin "20") (pinfunction "20_20") (pintype "passive"))
      (node (ref "U1") (pin "78") (pinfunction "PC10_78") (pintype "bidirectional"))
      (node (ref "U8") (pin "4") (pinfunction "D_4") (pintype "passive"))
    )
    (net (code "81") (name "/TXD5") (class "Default")
      (node (ref "J5") (pin "4") (pinfunction "4_4") (pintype "passive"))
      (node (ref "P17") (pin "19") (pinfunction "19_19") (pintype "passive"))
      (node (ref "U1") (pin "80") (pinfunction "PC12_80") (pintype "bidirectional"))
    )
    (net (code "82") (name "3V3") (class "Default")
      (node (ref "C14") (pin "2") (pinfunction "2_2") (pintype "passive"))
      (node (ref "C15") (pin "2") (pinfunction "2_2") (pintype "passive"))
      (node (ref "C16") (pin "2") (pinfunction "2_2") (pintype "passive"))
      (node (ref "C17") (pin "2") (pinfunction "2_2") (pintype "passive"))
      (node (ref "C23") (pin "1") (pinfunction "1_1") (pintype "passive"))
      (node (ref "C26") (pin "2") (pinfunction "2_2") (pintype "passive"))
      (node (ref "C27") (pin "2") (pinfunction "2_2") (pintype "passive"))
      (node (ref "C5") (pin "2") (pinfunction "2_2") (pintype "passive"))
      (node (ref "C6") (pin "2") (pinfunction "2_2") (pintype "passive"))
      (node (ref "C7") (pin "1") (pinfunction "1_1") (pintype "passive"))
      (node (ref "CB2") (pin "2") (pinfunction "2_2") (pintype "passive"))
      (node (ref "CB3") (pin "2") (pinfunction "2_2") (pintype "passive"))
      (node (ref "JP1") (pin "2") (pinfunction "2_2") (pintype "passive"))
      (node (ref "L1") (pin "1") (pinfunction "1_1") (pintype "passive"))
      (node (ref "P14") (pin "1") (pinfunction "1_1") (pintype "passive"))
      (node (ref "P16") (pin "3") (pinfunction "3_3") (pintype "passive"))
      (node (ref "P17") (pin "1") (pinfunction "1_1") (pintype "passive"))
      (node (ref "P7") (pin "2") (pinfunction "2_2") (pintype "passive"))
      (node (ref "P9") (pin "1") (pinfunction "1_1") (pintype "passive"))
      (node (ref "R19") (pin "2") (pinfunction "2_2") (pintype "passive"))
      (node (ref "R20") (pin "2") (pinfunction "2_2") (pintype "passive"))
      (node (ref "R3") (pin "1") (pinfunction "1_1") (pintype "passive"))
      (node (ref "U1") (pin "100") (pinfunction "VDD_100") (pintype "power_in"))
      (node (ref "U1") (pin "11") (pinfunction "VDD_11") (pintype "power_in"))
      (node (ref "U1") (pin "28") (pinfunction "VDD_28") (pintype "power_in"))
      (node (ref "U1") (pin "50") (pinfunction "VDD_50") (pintype "power_in"))
      (node (ref "U1") (pin "75") (pinfunction "VDD_75") (pintype "power_in"))
      (node (ref "U7") (pin "2") (pinfunction "OUT_2") (pintype "passive"))
      (node (ref "U8") (pin "8") (pinfunction "VDD_8") (pintype "passive"))
    )
    (net (code "83") (name "5V") (class "Default")
      (node (ref "C22") (pin "1") (pinfunction "1_1") (pintype "passive"))
      (node (ref "C3") (pin "1") (pinfunction "1_1") (pintype "passive"))
      (node (ref "C4") (pin "2") (pinfunction "2_2") (pintype "passive"))
      (node (ref "CB1") (pin "2") (pinfunction "2_2") (pintype "passive"))
      (node (ref "J2") (pin "1") (pinfunction "1_1") (pintype "passive"))
      (node (ref "J3") (pin "1") (pinfunction "1_1") (pintype "passive"))
      (node (ref "J4") (pin "1") (pinfunction "1_1") (pintype "passive"))
      (node (ref "J5") (pin "1") (pinfunction "1_1") (pintype "passive"))
      (node (ref "J6") (pin "1") (pinfunction "1_1") (pintype "passive"))
      (node (ref "P11") (pin "1") (pinfunction "1_1") (pintype "passive"))
      (node (ref "P2") (pin "1") (pinfunction "1_1") (pintype "passive"))
      (node (ref "R1") (pin "2") (pinfunction "2_2") (pintype "passive"))
      (node (ref "R4") (pin "1") (pinfunction "1_1") (pintype "passive"))
      (node (ref "U6") (pin "3") (pinfunction "OUT_3") (pintype "power_in"))
      (node (ref "U7") (pin "3") (pinfunction "IN_3") (pintype "passive"))
    )
    (net (code "84") (name "GND") (class "Default")
      (node (ref "BT1") (pin "2") (pinfunction "-_2") (pintype "passive"))
      (node (ref "C1") (pin "2") (pinfunction "2_2") (pintype "passive"))
      (node (ref "C10") (pin "2") (pinfunction "2_2") (pintype "passive"))
      (node (ref "C11") (pin "2") (pinfunction "2_2") (pintype "passive"))
      (node (ref "C12") (pin "2") (pinfunction "2_2") (pintype "passive"))
      (node (ref "C13") (pin "1") (pinfunction "1_1") (pintype "passive"))
      (node (ref "C14") (pin "1") (pinfunction "1_1") (pintype "passive"))
      (node (ref "C15") (pin "1") (pinfunction "1_1") (pintype "passive"))
      (node (ref "C16") (pin "1") (pinfunction "1_1") (pintype "passive"))
      (node (ref "C17") (pin "1") (pinfunction "1_1") (pintype "passive"))
      (node (ref "C18") (pin "1") (pinfunction "1_1") (pintype "passive"))
      (node (ref "C19") (pin "1") (pinfunction "1_1") (pintype "passive"))
      (node (ref "C2") (pin "1") (pinfunction "1_1") (pintype "passive"))
      (node (ref "C20") (pin "1") (pinfunction "1_1") (pintype "passive"))
      (node (ref "C21") (pin "1") (pinfunction "1_1") (pintype "passive"))
      (node (ref "C22") (pin "2") (pinfunction "2_2") (pintype "passive"))
      (node (ref "C23") (pin "2") (pinfunction "2_2") (pintype "passive"))
      (node (ref "C24") (pin "1") (pinfunction "1_1") (pintype "passive"))
      (node (ref "C25") (pin "1") (pinfunction "1_1") (pintype "passive"))
      (node (ref "C26") (pin "1") (pinfunction "1_1") (pintype "passive"))
      (node (ref "C27") (pin "1") (pinfunction "1_1") (pintype "passive"))
      (node (ref "C28") (pin "1") (pinfunction "1_1") (pintype "passive"))
      (node (ref "C29") (pin "1") (pinfunction "1_1") (pintype "passive"))
      (node (ref "C3") (pin "2") (pinfunction "2_2") (pintype "passive"))
      (node (ref "C30") (pin "1") (pinfunction "1_1") (pintype "passive"))
      (node (ref "C4") (pin "1") (pinfunction "1_1") (pintype "passive"))
      (node (ref "C5") (pin "1") (pinfunction "1_1") (pintype "passive"))
      (node (ref "C6") (pin "1") (pinfunction "1_1") (pintype "passive"))
      (node (ref "C7") (pin "2") (pinfunction "2_2") (pintype "passive"))
      (node (ref "C8") (pin "1") (pinfunction "1_1") (pintype "passive"))
      (node (ref "C9") (pin "1") (pinfunction "1_1") (pintype "passive"))
      (node (ref "CB4") (pin "2") (pinfunction "2_2") (pintype "passive"))
      (node (ref "J1") (pin "2") (pinfunction "2_2") (pintype "passive"))
      (node (ref "J2") (pin "2") (pinfunction "2_2") (pintype "passive"))
      (node (ref "J3") (pin "2") (pinfunction "2_2") (pintype "passive"))
      (node (ref "J4") (pin "2") (pinfunction "2_2") (pintype "passive"))
      (node (ref "J5") (pin "2") (pinfunction "2_2") (pintype "passive"))
      (node (ref "J6") (pin "2") (pinfunction "2_2") (pintype "passive"))
      (node (ref "LD1") (pin "2") (pintype "passive"))
      (node (ref "P1") (pin "3") (pinfunction "3_3") (pintype "passive"))
      (node (ref "P1") (pin "4") (pinfunction "4_4") (pintype "passive"))
      (node (ref "P10") (pin "10") (pinfunction "10_10") (pintype "passive"))
      (node (ref "P11") (pin "2") (pinfunction "2_2") (pintype "passive"))
      (node (ref "P14") (pin "2") (pinfunction "2_2") (pintype "passive"))
      (node (ref "P16") (pin "1") (pinfunction "1_1") (pintype "passive"))
      (node (ref "P17") (pin "2") (pinfunction "2_2") (pintype "passive"))
      (node (ref "P2") (pin "2") (pinfunction "2_2") (pintype "passive"))
      (node (ref "P3") (pin "1") (pinfunction "1_1") (pintype "passive"))
      (node (ref "P4") (pin "1") (pinfunction "1_1") (pintype "passive"))
      (node (ref "P5") (pin "1") (pinfunction "1_1") (pintype "passive"))
      (node (ref "P6") (pin "1") (pinfunction "1_1") (pintype "passive"))
      (node (ref "P7") (pin "1") (pinfunction "1_1") (pintype "passive"))
      (node (ref "P9") (pin "3") (pinfunction "3_3") (pintype "passive"))
      (node (ref "R18") (pin "1") (pinfunction "1_1") (pintype "passive"))
      (node (ref "S2") (pin "1") (pinfunction "1_1") (pintype "passive"))
      (node (ref "S3") (pin "1") (pinfunction "1_1") (pintype "passive"))
      (node (ref "S4") (pin "1") (pinfunction "1_1") (pintype "passive"))
      (node (ref "U1") (pin "10") (pinfunction "VSS_10") (pintype "power_in"))
      (node (ref "U1") (pin "20") (pinfunction "VSSA_20") (pintype "power_in"))
      (node (ref "U1") (pin "27") (pinfunction "VSS_27") (pintype "power_in"))
      (node (ref "U1") (pin "74") (pinfunction "VSS_74") (pintype "power_in"))
      (node (ref "U1") (pin "99") (pinfunction "VSS_99") (pintype "power_in"))
      (node (ref "U2") (pin "4") (pinfunction "GND_4") (pintype "power_in"))
      (node (ref "U3") (pin "4") (pinfunction "GND_4") (pintype "power_in"))
      (node (ref "U4") (pin "4") (pinfunction "GND_4") (pintype "power_in"))
      (node (ref "U5") (pin "4") (pinfunction "GND_4") (pintype "power_in"))
      (node (ref "U6") (pin "2") (pinfunction "GND_2") (pintype "power_in"))
      (node (ref "U7") (pin "1") (pinfunction "GND_1") (pintype "passive"))
      (node (ref "U8") (pin "5") (pinfunction "GND_5") (pintype "passive"))
    )
    (net (code "85") (name "Net-(BT1-+)") (class "Default")
      (node (ref "BT1") (pin "1") (pinfunction "+_1") (pintype "passive"))
      (node (ref "C13") (pin "2") (pinfunction "2_2") (pintype "passive"))
      (node (ref "JP1") (pin "1") (pinfunction "1_1") (pintype "passive"))
      (node (ref "U1") (pin "6") (pinfunction "VBAT_6") (pintype "power_in"))
    )
    (net (code "86") (name "Net-(CB1-Pad1)") (class "Default")
      (node (ref "CB1") (pin "1") (pinfunction "1_1") (pintype "passive"))
      (node (ref "CB2") (pin "1") (pinfunction "1_1") (pintype "passive"))
      (node (ref "P3") (pin "4") (pinfunction "4_4") (pintype "passive"))
      (node (ref "P4") (pin "4") (pinfunction "4_4") (pintype "passive"))
      (node (ref "P5") (pin "4") (pinfunction "4_4") (pintype "passive"))
      (node (ref "P6") (pin "4") (pinfunction "4_4") (pintype "passive"))
      (node (ref "R21") (pin "2") (pinfunction "2_2") (pintype "passive"))
      (node (ref "R22") (pin "2") (pinfunction "2_2") (pintype "passive"))
      (node (ref "R23") (pin "2") (pinfunction "2_2") (pintype "passive"))
      (node (ref "R24") (pin "2") (pinfunction "2_2") (pintype "passive"))
      (node (ref "R25") (pin "2") (pinfunction "2_2") (pintype "passive"))
      (node (ref "R26") (pin "2") (pinfunction "2_2") (pintype "passive"))
      (node (ref "R27") (pin "2") (pinfunction "2_2") (pintype "passive"))
      (node (ref "R28") (pin "2") (pinfunction "2_2") (pintype "passive"))
    )
    (net (code "87") (name "Net-(CB3-Pad1)") (class "Default")
      (node (ref "CB3") (pin "1") (pinfunction "1_1") (pintype "passive"))
      (node (ref "P13") (pin "1") (pinfunction "1_1") (pintype "passive"))
      (node (ref "P13") (pin "11") (pinfunction "11_11") (pintype "passive"))
      (node (ref "P13") (pin "13") (pinfunction "13_13") (pintype "passive"))
      (node (ref "P13") (pin "15") (pinfunction "15_15") (pintype "passive"))
      (node (ref "P13") (pin "17") (pinfunction "17_17") (pintype "passive"))
      (node (ref "P13") (pin "19") (pinfunction "19_19") (pintype "passive"))
      (node (ref "P13") (pin "21") (pinfunction "21_21") (pintype "passive"))
      (node (ref "P13") (pin "23") (pinfunction "23_23") (pintype "passive"))
      (node (ref "P13") (pin "3") (pinfunction "3_3") (pintype "passive"))
      (node (ref "P13") (pin "5") (pinfunction "5_5") (pintype "passive"))
      (node (ref "P13") (pin "7") (pinfunction "7_7") (pintype "passive"))
      (node (ref "P13") (pin "9") (pinfunction "9_9") (pintype "passive"))
      (node (ref "P15") (pin "1") (pinfunction "1_1") (pintype "passive"))
    )
    (net (code "88") (name "Net-(CB4-Pad1)") (class "Default")
      (node (ref "CB4") (pin "1") (pinfunction "1_1") (pintype "passive"))
      (node (ref "P12") (pin "1") (pinfunction "1_1") (pintype "passive"))
      (node (ref "P12") (pin "10") (pinfunction "10_10") (pintype "passive"))
      (node (ref "P12") (pin "11") (pinfunction "11_11") (pintype "passive"))
      (node (ref "P12") (pin "12") (pinfunction "12_12") (pintype "passive"))
      (node (ref "P12") (pin "2") (pinfunction "2_2") (pintype "passive"))
      (node (ref "P12") (pin "3") (pinfunction "3_3") (pintype "passive"))
      (node (ref "P12") (pin "4") (pinfunction "4_4") (pintype "passive"))
      (node (ref "P12") (pin "5") (pinfunction "5_5") (pintype "passive"))
      (node (ref "P12") (pin "6") (pinfunction "6_6") (pintype "passive"))
      (node (ref "P12") (pin "7") (pinfunction "7_7") (pintype "passive"))
      (node (ref "P12") (pin "8") (pinfunction "8_8") (pintype "passive"))
      (node (ref "P12") (pin "9") (pinfunction "9_9") (pintype "passive"))
      (node (ref "P15") (pin "2") (pinfunction "2_2") (pintype "passive"))
    )
    (net (code "89") (name "Net-(LD1-Pad1)") (class "Default")
      (node (ref "LD1") (pin "1") (pintype "passive"))
      (node (ref "R1") (pin "1") (pinfunction "1_1") (pintype "passive"))
    )
    (net (code "90") (name "Net-(LD2-Pad1)") (class "Default")
      (node (ref "LD2") (pin "1") (pintype "passive"))
      (node (ref "R19") (pin "1") (pinfunction "1_1") (pintype "passive"))
    )
    (net (code "91") (name "Net-(LD3-Pad1)") (class "Default")
      (node (ref "LD3") (pin "1") (pintype "passive"))
      (node (ref "R20") (pin "1") (pinfunction "1_1") (pintype "passive"))
    )
    (net (code "92") (name "Net-(P1-Pad1)") (class "Default")
      (node (ref "P1") (pin "1") (pinfunction "1_1") (pintype "passive"))
      (node (ref "R2") (pin "2") (pinfunction "2_2") (pintype "passive"))
    )
    (net (code "93") (name "Net-(P1-Pad2)") (class "Default")
      (node (ref "P1") (pin "2") (pinfunction "2_2") (pintype "passive"))
      (node (ref "R5") (pin "1") (pinfunction "1_1") (pintype "passive"))
    )
    (net (code "94") (name "Net-(P1-Pad6)") (class "Default")
      (node (ref "P1") (pin "6") (pinfunction "6_6") (pintype "passive"))
      (node (ref "R6") (pin "1") (pinfunction "1_1") (pintype "passive"))
    )
    (net (code "95") (name "Net-(P1-Pad7)") (class "Default")
      (node (ref "P1") (pin "7") (pinfunction "7_7") (pintype "passive"))
      (node (ref "P1") (pin "8") (pinfunction "8_8") (pintype "passive"))
      (node (ref "R3") (pin "2") (pinfunction "2_2") (pintype "passive"))
    )
    (net (code "96") (name "Net-(P1-Pad10)") (class "Default")
      (node (ref "P1") (pin "10") (pinfunction "10_10") (pintype "passive"))
      (node (ref "P1") (pin "9") (pinfunction "9_9") (pintype "passive"))
      (node (ref "R4") (pin "2") (pinfunction "2_2") (pintype "passive"))
    )
    (net (code "97") (name "Net-(P3-Pad2)") (class "Default")
      (node (ref "P3") (pin "2") (pinfunction "2_2") (pintype "passive"))
      (node (ref "P8") (pin "2") (pinfunction "2_2") (pintype "passive"))
      (node (ref "R28") (pin "1") (pinfunction "1_1") (pintype "passive"))
    )
    (net (code "98") (name "Net-(P3-Pad3)") (class "Default")
      (node (ref "P3") (pin "3") (pinfunction "3_3") (pintype "passive"))
      (node (ref "P8") (pin "4") (pinfunction "4_4") (pintype "passive"))
      (node (ref "R27") (pin "1") (pinfunction "1_1") (pintype "passive"))
    )
    (net (code "99") (name "Net-(P4-Pad2)") (class "Default")
      (node (ref "P4") (pin "2") (pinfunction "2_2") (pintype "passive"))
      (node (ref "P8") (pin "6") (pinfunction "6_6") (pintype "passive"))
      (node (ref "R22") (pin "1") (pinfunction "1_1") (pintype "passive"))
    )
    (net (code "100") (name "Net-(P4-Pad3)") (class "Default")
      (node (ref "P4") (pin "3") (pinfunction "3_3") (pintype "passive"))
      (node (ref "P8") (pin "8") (pinfunction "8_8") (pintype "passive"))
      (node (ref "R21") (pin "1") (pinfunction "1_1") (pintype "passive"))
    )
    (net (code "101") (name "Net-(P5-Pad2)") (class "Default")
      (node (ref "P5") (pin "2") (pinfunction "2_2") (pintype "passive"))
      (node (ref "P8") (pin "22") (pinfunction "22_22") (pintype "passive"))
      (node (ref "R24") (pin "1") (pinfunction "1_1") (pintype "passive"))
    )
    (net (code "102") (name "Net-(P5-Pad3)") (class "Default")
      (node (ref "P5") (pin "3") (pinfunction "3_3") (pintype "passive"))
      (node (ref "P8") (pin "24") (pinfunction "24_24") (pintype "passive"))
      (node (ref "R23") (pin "1") (pinfunction "1_1") (pintype "passive"))
    )
    (net (code "103") (name "Net-(P6-Pad2)") (class "Default")
      (node (ref "P6") (pin "2") (pinfunction "2_2") (pintype "passive"))
      (node (ref "P8") (pin "30") (pinfunction "30_30") (pintype "passive"))
      (node (ref "R26") (pin "1") (pinfunction "1_1") (pintype "passive"))
    )
    (net (code "104") (name "Net-(P6-Pad3)") (class "Default")
      (node (ref "P6") (pin "3") (pinfunction "3_3") (pintype "passive"))
      (node (ref "P8") (pin "32") (pinfunction "32_32") (pintype "passive"))
      (node (ref "R25") (pin "1") (pinfunction "1_1") (pintype "passive"))
    )
    (net (code "105") (name "Net-(P9-Pad2)") (class "Default")
      (node (ref "P9") (pin "2") (pinfunction "2_2") (pintype "passive"))
      (node (ref "U1") (pin "19") (pinfunction "VDD_19") (pintype "power_in"))
    )
    (net (code "106") (name "Net-(S1-NO)") (class "Default")
      (node (ref "F1") (pin "1") (pinfunction "1_1") (pintype "passive"))
      (node (ref "S1") (pin "2") (pinfunction "NO_2") (pintype "passive"))
    )
    (net (code "107") (name "Net-(U1A-PC14-OSC32_IN(PC14))") (class "Default")
      (node (ref "C8") (pin "2") (pinfunction "2_2") (pintype "passive"))
      (node (ref "U1") (pin "8") (pinfunction "PC14-OSC32_IN(PC14)_8") (pintype "bidirectional"))
      (node (ref "Y1") (pin "2") (pinfunction "2_2") (pintype "passive"))
    )
    (net (code "108") (name "Net-(U1A-PC15-OSC32_OUT(PC15))") (class "Default")
      (node (ref "C9") (pin "2") (pinfunction "2_2") (pintype "passive"))
      (node (ref "U1") (pin "9") (pinfunction "PC15-OSC32_OUT(PC15)_9") (pintype "bidirectional"))
      (node (ref "Y1") (pin "1") (pinfunction "1_1") (pintype "passive"))
    )
    (net (code "109") (name "Net-(U1A-PH0-OSC_IN(PH0))") (class "Default")
      (node (ref "C10") (pin "1") (pinfunction "1_1") (pintype "passive"))
      (node (ref "U1") (pin "12") (pinfunction "PH0-OSC_IN(PH0)_12") (pintype "bidirectional"))
      (node (ref "Y2") (pin "2") (pinfunction "2_2") (pintype "passive"))
    )
    (net (code "110") (name "Net-(U1A-PH1-OSC_OUT(PH1))") (class "Default")
      (node (ref "C11") (pin "1") (pinfunction "1_1") (pintype "passive"))
      (node (ref "U1") (pin "13") (pinfunction "PH1-OSC_OUT(PH1)_13") (pintype "bidirectional"))
      (node (ref "Y2") (pin "1") (pinfunction "1_1") (pintype "passive"))
    )
    (net (code "111") (name "Net-(U1A-VCAP_1)") (class "Default")
      (node (ref "C30") (pin "2") (pinfunction "2_2") (pintype "passive"))
      (node (ref "U1") (pin "49") (pinfunction "VCAP_1_49") (pintype "power_in"))
    )
    (net (code "112") (name "Net-(U1A-VCAP_2)") (class "Default")
      (node (ref "C29") (pin "2") (pinfunction "2_2") (pintype "passive"))
      (node (ref "U1") (pin "73") (pinfunction "VCAP_2_73") (pintype "power_in"))
    )
    (net (code "113") (name "Net-(U1B-VDDA)") (class "Default")
      (node (ref "C28") (pin "2") (pinfunction "2_2") (pintype "passive"))
      (node (ref "L1") (pin "2") (pinfunction "2_2") (pintype "passive"))
      (node (ref "U1") (pin "21") (pinfunction "VREF+_21") (pintype "power_in"))
      (node (ref "U1") (pin "22") (pinfunction "VDDA_22") (pintype "power_in"))
    )
    (net (code "114") (name "Net-(U2-EF)") (class "Default")
      (node (ref "P8") (pin "26") (pinfunction "26_26") (pintype "passive"))
      (node (ref "U2") (pin "2") (pinfunction "EF_2") (pintype "open_collector"))
    )
    (net (code "115") (name "Net-(U2-IN1)") (class "Default")
      (node (ref "P8") (pin "28") (pinfunction "28_28") (pintype "passive"))
      (node (ref "U2") (pin "3") (pinfunction "IN1_3") (pintype "input"))
    )
    (net (code "116") (name "Net-(U2-IN2)") (class "Default")
      (node (ref "P8") (pin "10") (pinfunction "10_10") (pintype "passive"))
      (node (ref "U2") (pin "5") (pinfunction "IN2_5") (pintype "input"))
    )
    (net (code "117") (name "Net-(U2-OUT1)") (class "Default")
      (node (ref "JP2") (pin "1") (pinfunction "1_1") (pintype "passive"))
      (node (ref "U2") (pin "1") (pinfunction "OUT1_1") (pintype "power_in"))
    )
    (net (code "118") (name "Net-(U2-OUT2)") (class "Default")
      (node (ref "JP2") (pin "2") (pinfunction "2_2") (pintype "passive"))
      (node (ref "U2") (pin "7") (pinfunction "OUT2_7") (pintype "power_in"))
    )
    (net (code "119") (name "Net-(U3-EF)") (class "Default")
      (node (ref "P8") (pin "34") (pinfunction "34_34") (pintype "passive"))
      (node (ref "U3") (pin "2") (pinfunction "EF_2") (pintype "open_collector"))
    )
    (net (code "120") (name "Net-(U3-IN1)") (class "Default")
      (node (ref "P8") (pin "36") (pinfunction "36_36") (pintype "passive"))
      (node (ref "U3") (pin "3") (pinfunction "IN1_3") (pintype "input"))
    )
    (net (code "121") (name "Net-(U3-IN2)") (class "Default")
      (node (ref "P8") (pin "12") (pinfunction "12_12") (pintype "passive"))
      (node (ref "U3") (pin "5") (pinfunction "IN2_5") (pintype "input"))
    )
    (net (code "122") (name "Net-(U3-OUT1)") (class "Default")
      (node (ref "JP3") (pin "1") (pinfunction "1_1") (pintype "passive"))
      (node (ref "U3") (pin "1") (pinfunction "OUT1_1") (pintype "power_in"))
    )
    (net (code "123") (name "Net-(U3-OUT2)") (class "Default")
      (node (ref "JP3") (pin "2") (pinfunction "2_2") (pintype "passive"))
      (node (ref "U3") (pin "7") (pinfunction "OUT2_7") (pintype "power_in"))
    )
    (net (code "124") (name "Net-(U4-EF)") (class "Default")
      (node (ref "P8") (pin "18") (pinfunction "18_18") (pintype "passive"))
      (node (ref "U4") (pin "2") (pinfunction "EF_2") (pintype "open_collector"))
    )
    (net (code "125") (name "Net-(U4-IN1)") (class "Default")
      (node (ref "P8") (pin "20") (pinfunction "20_20") (pintype "passive"))
      (node (ref "U4") (pin "3") (pinfunction "IN1_3") (pintype "input"))
    )
    (net (code "126") (name "Net-(U4-IN2)") (class "Default")
      (node (ref "P8") (pin "14") (pinfunction "14_14") (pintype "passive"))
      (node (ref "U4") (pin "5") (pinfunction "IN2_5") (pintype "input"))
    )
    (net (code "127") (name "Net-(U4-OUT1)") (class "Default")
      (node (ref "JP4") (pin "1") (pinfunction "1_1") (pintype "passive"))
      (node (ref "U4") (pin "1") (pinfunction "OUT1_1") (pintype "power_in"))
    )
    (net (code "128") (name "Net-(U4-OUT2)") (class "Default")
      (node (ref "JP4") (pin "2") (pinfunction "2_2") (pintype "passive"))
      (node (ref "U4") (pin "7") (pinfunction "OUT2_7") (pintype "power_in"))
    )
    (net (code "129") (name "Net-(U5-EF)") (class "Default")
      (node (ref "P8") (pin "38") (pinfunction "38_38") (pintype "passive"))
      (node (ref "U5") (pin "2") (pinfunction "EF_2") (pintype "open_collector"))
    )
    (net (code "130") (name "Net-(U5-IN1)") (class "Default")
      (node (ref "P8") (pin "40") (pinfunction "40_40") (pintype "passive"))
      (node (ref "U5") (pin "3") (pinfunction "IN1_3") (pintype "input"))
    )
    (net (code "131") (name "Net-(U5-IN2)") (class "Default")
      (node (ref "P8") (pin "16") (pinfunction "16_16") (pintype "passive"))
      (node (ref "U5") (pin "5") (pinfunction "IN2_5") (pintype "input"))
    )
    (net (code "132") (name "Net-(U5-OUT1)") (class "Default")
      (node (ref "JP5") (pin "1") (pinfunction "1_1") (pintype "passive"))
      (node (ref "U5") (pin "1") (pinfunction "OUT1_1") (pintype "power_in"))
    )
    (net (code "133") (name "Net-(U5-OUT2)") (class "Default")
      (node (ref "JP5") (pin "2") (pinfunction "2_2") (pintype "passive"))
      (node (ref "U5") (pin "7") (pinfunction "OUT2_7") (pintype "power_in"))
    )
    (net (code "134") (name "Vbat") (class "Default")
      (node (ref "F1") (pin "2") (pinfunction "2_2") (pintype "passive"))
      (node (ref "J1") (pin "1") (pinfunction "1_1") (pintype "passive"))
    )
    (net (code "135") (name "Vss") (class "Default")
      (node (ref "C1") (pin "1") (pinfunction "1_1") (pintype "passive"))
      (node (ref "C18") (pin "2") (pinfunction "2_2") (pintype "passive"))
      (node (ref "C19") (pin "2") (pinfunction "2_2") (pintype "passive"))
      (node (ref "C2") (pin "2") (pinfunction "2_2") (pintype "passive"))
      (node (ref "C20") (pin "2") (pinfunction "2_2") (pintype "passive"))
      (node (ref "C21") (pin "2") (pinfunction "2_2") (pintype "passive"))
      (node (ref "R17") (pin "2") (pinfunction "2_2") (pintype "passive"))
      (node (ref "S1") (pin "1") (pinfunction "COMMON_1") (pintype "passive"))
      (node (ref "U2") (pin "6") (pinfunction "VS_6") (pintype "power_in"))
      (node (ref "U3") (pin "6") (pinfunction "VS_6") (pintype "power_in"))
      (node (ref "U4") (pin "6") (pinfunction "VS_6") (pintype "power_in"))
      (node (ref "U5") (pin "6") (pinfunction "VS_6") (pintype "power_in"))
      (node (ref "U6") (pin "1") (pinfunction "IN_1") (pintype "power_in"))
    )
    (net (code "136") (name "unconnected-(P1-Pad5)") (class "Default")
      (node (ref "P1") (pin "5") (pinfunction "5_5") (pintype "passive"))
    )
    (net (code "137") (name "unconnected-(P2-Pad5)") (class "Default")
      (node (ref "P2") (pin "5") (pinfunction "5_5") (pintype "passive"))
    )
    (net (code "138") (name "unconnected-(P2-Pad6)") (class "Default")
      (node (ref "P2") (pin "6") (pinfunction "6_6") (pintype "passive"))
    )
    (net (code "139") (name "unconnected-(P2-Pad9)") (class "Default")
      (node (ref "P2") (pin "9") (pinfunction "9_9") (pintype "passive"))
    )
    (net (code "140") (name "unconnected-(P2-Pad10)") (class "Default")
      (node (ref "P2") (pin "10") (pinfunction "10_10") (pintype "passive"))
    )
    (net (code "141") (name "unconnected-(U1A-PC13-Pad7)") (class "Default")
      (node (ref "U1") (pin "7") (pinfunction "PC13_7") (pintype "bidirectional"))
    )
  )
)
